# DA_uno_shield_0_9.net
KiCad netlist of a schematic drawn in EAGLE
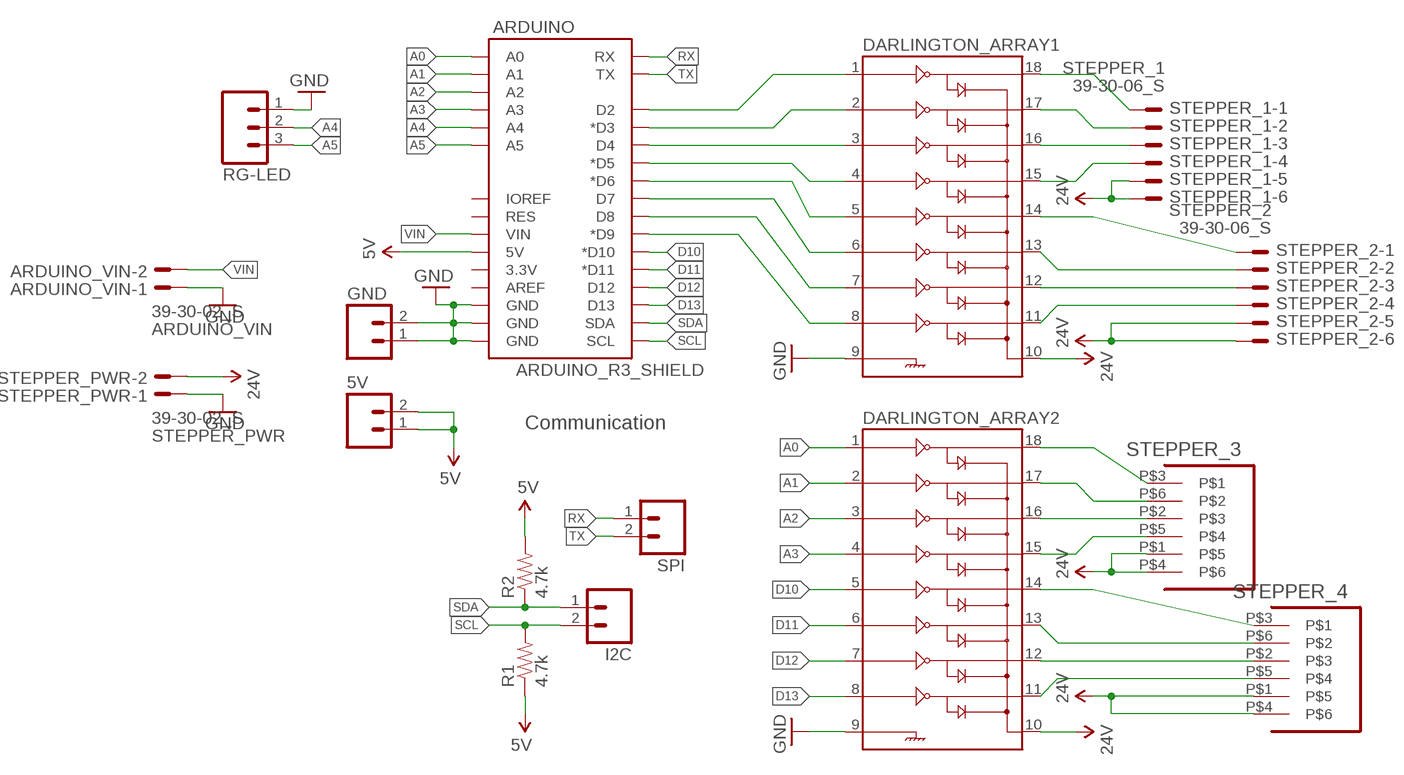
[diagram p0: schematic, sheet 1]

(export (version "E")
  (design (tool "Eeschema 10.0.6"))
  (components
    (comp (ref "5V")
      (value "M021X02_NO_SILK")
      (footprint "eagle-import:1X02_NO_SILK")
      (libsource (lib "eagle-import") (part "M021X02_NO_SILK"))
    )
    (comp (ref "ARDUINO")
      (value "ARDUINO_R3_SHIELD")
      (footprint "eagle-import:UNO_R3_SHIELD")
      (libsource (lib "eagle-import") (part "ARDUINO_R3_SHIELD"))
    )
    (comp (ref "ARDUINO_VIN")
      (value "39-30-02_S")
      (footprint "eagle-import:39-30-_02_")
      (libsource (lib "eagle-import") (part "39-30-?02?_S"))
    )
    (comp (ref "DARLINGTON_ARRAY1")
      (value "ULN2803DIP")
      (footprint "eagle-import:DIL18")
      (libsource (lib "eagle-import") (part "ULN2803DIP"))
    )
    (comp (ref "DARLINGTON_ARRAY2")
      (value "ULN2803DIP")
      (footprint "eagle-import:DIL18")
      (libsource (lib "eagle-import") (part "ULN2803DIP"))
    )
    (comp (ref "GND")
      (value "M021X02_NO_SILK")
      (footprint "eagle-import:1X02_NO_SILK")
      (libsource (lib "eagle-import") (part "M021X02_NO_SILK"))
    )
    (comp (ref "I2C")
      (value "M021X02_NO_SILK")
      (footprint "eagle-import:1X02_NO_SILK")
      (libsource (lib "eagle-import") (part "M021X02_NO_SILK"))
    )
    (comp (ref "R1")
      (value "4.7k")
      (footprint "eagle-import:AXIAL-0.3-KIT")
      (libsource (lib "eagle-import") (part "RESISTORKIT"))
    )
    (comp (ref "R2")
      (value "4.7k")
      (footprint "eagle-import:AXIAL-0.3-KIT")
      (libsource (lib "eagle-import") (part "RESISTORKIT"))
    )
    (comp (ref "RG-LED")
      (value "M03LOCK_NO_SILK")
      (footprint "eagle-import:1X03_LOCK_NO_SILK")
      (libsource (lib "eagle-import") (part "M03LOCK_NO_SILK"))
    )
    (comp (ref "SPI")
      (value "M021X02_NO_SILK")
      (footprint "eagle-import:1X02_NO_SILK")
      (libsource (lib "eagle-import") (part "M021X02_NO_SILK"))
    )
    (comp (ref "STEPPER_1")
      (value "39-30-06_S")
      (footprint "eagle-import:39-30-_06_")
      (libsource (lib "eagle-import") (part "39-30-?06?_S"))
    )
    (comp (ref "STEPPER_2")
      (value "39-30-06_S")
      (footprint "eagle-import:39-30-_06_")
      (libsource (lib "eagle-import") (part "39-30-?06?_S"))
    )
    (comp (ref "STEPPER_3")
      (value "39-29-06")
      (footprint "eagle-import:39-29-_06_")
      (libsource (lib "eagle-import") (part "39-29-?06?"))
    )
    (comp (ref "STEPPER_4")
      (value "39-29-06")
      (footprint "eagle-import:39-29-_06_")
      (libsource (lib "eagle-import") (part "39-29-?06?"))
    )
    (comp (ref "STEPPER_PWR")
      (value "39-30-02_S")
      (footprint "eagle-import:39-30-_02_")
      (libsource (lib "eagle-import") (part "39-30-?02?_S"))
    )
  )
  (nets
    (net (code "1") (name "5V") (class "Default")
      (node (ref "5V") (pin "1") (pinfunction "1_1") (pintype "passive"))
      (node (ref "5V") (pin "2") (pinfunction "2_2") (pintype "passive"))
      (node (ref "ARDUINO") (pin "5V") (pinfunction "5V_5V") (pintype "bidirectional"))
      (node (ref "R1") (pin "P$1") (pinfunction "1_P$1") (pintype "passive"))
      (node (ref "R2") (pin "P$2") (pinfunction "2_P$2") (pintype "passive"))
    )
    (net (code "2") (name "24V") (class "Default")
      (node (ref "DARLINGTON_ARRAY1") (pin "10") (pinfunction "10_10") (pintype "bidirectional"))
      (node (ref "DARLINGTON_ARRAY2") (pin "10") (pinfunction "10_10") (pintype "bidirectional"))
      (node (ref "STEPPER_1") (pin "5") (pinfunction "P_5") (pintype "passive"))
      (node (ref "STEPPER_1") (pin "6") (pinfunction "P_6") (pintype "passive"))
      (node (ref "STEPPER_2") (pin "5") (pinfunction "P_5") (pintype "passive"))
      (node (ref "STEPPER_2") (pin "6") (pinfunction "P_6") (pintype "passive"))
      (node (ref "STEPPER_3") (pin "P$1") (pinfunction "P$5_P$1") (pintype "bidirectional"))
      (node (ref "STEPPER_3") (pin "P$4") (pinfunction "P$6_P$4") (pintype "bidirectional"))
      (node (ref "STEPPER_4") (pin "P$1") (pinfunction "P$5_P$1") (pintype "bidirectional"))
      (node (ref "STEPPER_4") (pin "P$4") (pinfunction "P$6_P$4") (pintype "bidirectional"))
      (node (ref "STEPPER_PWR") (pin "2") (pinfunction "P_2") (pintype "passive"))
    )
    (net (code "3") (name "A0") (class "Default")
      (node (ref "ARDUINO") (pin "A0") (pinfunction "A0_A0") (pintype "bidirectional"))
      (node (ref "DARLINGTON_ARRAY2") (pin "1") (pinfunction "1_1") (pintype "bidirectional"))
    )
    (net (code "4") (name "A1") (class "Default")
      (node (ref "ARDUINO") (pin "A1") (pinfunction "A1_A1") (pintype "bidirectional"))
      (node (ref "DARLINGTON_ARRAY2") (pin "2") (pinfunction "2_2") (pintype "bidirectional"))
    )
    (net (code "5") (name "A2") (class "Default")
      (node (ref "ARDUINO") (pin "A2") (pinfunction "A2_A2") (pintype "bidirectional"))
      (node (ref "DARLINGTON_ARRAY2") (pin "3") (pinfunction "3_3") (pintype "bidirectional"))
    )
    (net (code "6") (name "A3") (class "Default")
      (node (ref "ARDUINO") (pin "A3") (pinfunction "A3_A3") (pintype "bidirectional"))
      (node (ref "DARLINGTON_ARRAY2") (pin "4") (pinfunction "4_4") (pintype "bidirectional"))
    )
    (net (code "7") (name "A4") (class "Default")
      (node (ref "ARDUINO") (pin "A4") (pinfunction "A4_A4") (pintype "bidirectional"))
      (node (ref "RG-LED") (pin "2") (pinfunction "2_2") (pintype "passive"))
    )
    (net (code "8") (name "A5") (class "Default")
      (node (ref "ARDUINO") (pin "A5") (pinfunction "A5_A5") (pintype "bidirectional"))
      (node (ref "RG-LED") (pin "3") (pinfunction "3_3") (pintype "passive"))
    )
    (net (code "9") (name "D10") (class "Default")
      (node (ref "ARDUINO") (pin "D10") (pinfunction "*D10_D10") (pintype "bidirectional"))
      (node (ref "DARLINGTON_ARRAY2") (pin "5") (pinfunction "5_5") (pintype "bidirectional"))
    )
    (net (code "10") (name "D11") (class "Default")
      (node (ref "ARDUINO") (pin "D11") (pinfunction "*D11_D11") (pintype "bidirectional"))
      (node (ref "DARLINGTON_ARRAY2") (pin "6") (pinfunction "6_6") (pintype "bidirectional"))
    )
    (net (code "11") (name "D12") (class "Default")
      (node (ref "ARDUINO") (pin "D12") (pinfunction "D12_D12") (pintype "bidirectional"))
      (node (ref "DARLINGTON_ARRAY2") (pin "7") (pinfunction "7_7") (pintype "bidirectional"))
    )
    (net (code "12") (name "D13") (class "Default")
      (node (ref "ARDUINO") (pin "D13") (pinfunction "D13_D13") (pintype "bidirectional"))
      (node (ref "DARLINGTON_ARRAY2") (pin "8") (pinfunction "8_8") (pintype "bidirectional"))
    )
    (net (code "13") (name "GND") (class "Default")
      (node (ref "ARDUINO") (pin "GND@0") (pinfunction "GND_GND@0") (pintype "bidirectional"))
      (node (ref "ARDUINO") (pin "GND@1") (pinfunction "GND_GND@1") (pintype "bidirectional"))
      (node (ref "ARDUINO") (pin "GND@2") (pinfunction "GND_GND@2") (pintype "bidirectional"))
      (node (ref "ARDUINO_VIN") (pin "1") (pinfunction "P_1") (pintype "passive"))
      (node (ref "DARLINGTON_ARRAY1") (pin "9") (pinfunction "9_9") (pintype "bidirectional"))
      (node (ref "DARLINGTON_ARRAY2") (pin "9") (pinfunction "9_9") (pintype "bidirectional"))
      (node (ref "GND") (pin "1") (pinfunction "1_1") (pintype "passive"))
      (node (ref "GND") (pin "2") (pinfunction "2_2") (pintype "passive"))
      (node (ref "RG-LED") (pin "1") (pinfunction "1_1") (pintype "passive"))
      (node (ref "STEPPER_PWR") (pin "1") (pinfunction "P_1") (pintype "passive"))
    )
    (net (code "14") (name "Net-(ARDUINO-*D3)") (class "Default")
      (node (ref "ARDUINO") (pin "D3") (pinfunction "*D3_D3") (pintype "bidirectional"))
      (node (ref "DARLINGTON_ARRAY1") (pin "2") (pinfunction "2_2") (pintype "bidirectional"))
    )
    (net (code "15") (name "Net-(ARDUINO-*D5)") (class "Default")
      (node (ref "ARDUINO") (pin "D5") (pinfunction "*D5_D5") (pintype "bidirectional"))
      (node (ref "DARLINGTON_ARRAY1") (pin "4") (pinfunction "4_4") (pintype "bidirectional"))
    )
    (net (code "16") (name "Net-(ARDUINO-*D6)") (class "Default")
      (node (ref "ARDUINO") (pin "D6") (pinfunction "*D6_D6") (pintype "bidirectional"))
      (node (ref "DARLINGTON_ARRAY1") (pin "5") (pinfunction "5_5") (pintype "bidirectional"))
    )
    (net (code "17") (name "Net-(ARDUINO-*D9)") (class "Default")
      (node (ref "ARDUINO") (pin "D9") (pinfunction "*D9_D9") (pintype "bidirectional"))
      (node (ref "DARLINGTON_ARRAY1") (pin "8") (pinfunction "8_8") (pintype "bidirectional"))
    )
    (net (code "18") (name "Net-(ARDUINO-PadD2)") (class "Default")
      (node (ref "ARDUINO") (pin "D2") (pinfunction "D2_D2") (pintype "bidirectional"))
      (node (ref "DARLINGTON_ARRAY1") (pin "1") (pinfunction "1_1") (pintype "bidirectional"))
    )
    (net (code "19") (name "Net-(ARDUINO-PadD4)") (class "Default")
      (node (ref "ARDUINO") (pin "D4") (pinfunction "D4_D4") (pintype "bidirectional"))
      (node (ref "DARLINGTON_ARRAY1") (pin "3") (pinfunction "3_3") (pintype "bidirectional"))
    )
    (net (code "20") (name "Net-(ARDUINO-PadD7)") (class "Default")
      (node (ref "ARDUINO") (pin "D7") (pinfunction "D7_D7") (pintype "bidirectional"))
      (node (ref "DARLINGTON_ARRAY1") (pin "6") (pinfunction "6_6") (pintype "bidirectional"))
    )
    (net (code "21") (name "Net-(ARDUINO-PadD8)") (class "Default")
      (node (ref "ARDUINO") (pin "D8") (pinfunction "D8_D8") (pintype "bidirectional"))
      (node (ref "DARLINGTON_ARRAY1") (pin "7") (pinfunction "7_7") (pintype "bidirectional"))
    )
    (net (code "22") (name "Net-(STEPPER_1A-P)") (class "Default")
      (node (ref "DARLINGTON_ARRAY1") (pin "18") (pinfunction "18_18") (pintype "bidirectional"))
      (node (ref "STEPPER_1") (pin "1") (pinfunction "P_1") (pintype "passive"))
    )
    (net (code "23") (name "Net-(STEPPER_1B-P)") (class "Default")
      (node (ref "DARLINGTON_ARRAY1") (pin "17") (pinfunction "17_17") (pintype "bidirectional"))
      (node (ref "STEPPER_1") (pin "2") (pinfunction "P_2") (pintype "passive"))
    )
    (net (code "24") (name "Net-(STEPPER_1C-P)") (class "Default")
      (node (ref "DARLINGTON_ARRAY1") (pin "16") (pinfunction "16_16") (pintype "bidirectional"))
      (node (ref "STEPPER_1") (pin "3") (pinfunction "P_3") (pintype "passive"))
    )
    (net (code "25") (name "Net-(STEPPER_1D-P)") (class "Default")
      (node (ref "DARLINGTON_ARRAY1") (pin "15") (pinfunction "15_15") (pintype "bidirectional"))
      (node (ref "STEPPER_1") (pin "4") (pinfunction "P_4") (pintype "passive"))
    )
    (net (code "26") (name "Net-(STEPPER_2A-P)") (class "Default")
      (node (ref "DARLINGTON_ARRAY1") (pin "14") (pinfunction "14_14") (pintype "bidirectional"))
      (node (ref "STEPPER_2") (pin "1") (pinfunction "P_1") (pintype "passive"))
    )
    (net (code "27") (name "Net-(STEPPER_2B-P)") (class "Default")
      (node (ref "DARLINGTON_ARRAY1") (pin "13") (pinfunction "13_13") (pintype "bidirectional"))
      (node (ref "STEPPER_2") (pin "2") (pinfunction "P_2") (pintype "passive"))
    )
    (net (code "28") (name "Net-(STEPPER_2C-P)") (class "Default")
      (node (ref "DARLINGTON_ARRAY1") (pin "12") (pinfunction "12_12") (pintype "bidirectional"))
      (node (ref "STEPPER_2") (pin "3") (pinfunction "P_3") (pintype "passive"))
    )
    (net (code "29") (name "Net-(STEPPER_2D-P)") (class "Default")
      (node (ref "DARLINGTON_ARRAY1") (pin "11") (pinfunction "11_11") (pintype "bidirectional"))
      (node (ref "STEPPER_2") (pin "4") (pinfunction "P_4") (pintype "passive"))
    )
    (net (code "30") (name "Net-(STEPPER_3-P$1)") (class "Default")
      (node (ref "DARLINGTON_ARRAY2") (pin "18") (pinfunction "18_18") (pintype "bidirectional"))
      (node (ref "STEPPER_3") (pin "P$3") (pinfunction "P$1_P$3") (pintype "bidirectional"))
    )
    (net (code "31") (name "Net-(STEPPER_3-P$2)") (class "Default")
      (node (ref "DARLINGTON_ARRAY2") (pin "17") (pinfunction "17_17") (pintype "bidirectional"))
      (node (ref "STEPPER_3") (pin "P$6") (pinfunction "P$2_P$6") (pintype "bidirectional"))
    )
    (net (code "32") (name "Net-(STEPPER_3-P$3)") (class "Default")
      (node (ref "DARLINGTON_ARRAY2") (pin "16") (pinfunction "16_16") (pintype "bidirectional"))
      (node (ref "STEPPER_3") (pin "P$2") (pinfunction "P$3_P$2") (pintype "bidirectional"))
    )
    (net (code "33") (name "Net-(STEPPER_3-P$4)") (class "Default")
      (node (ref "DARLINGTON_ARRAY2") (pin "15") (pinfunction "15_15") (pintype "bidirectional"))
      (node (ref "STEPPER_3") (pin "P$5") (pinfunction "P$4_P$5") (pintype "bidirectional"))
    )
    (net (code "34") (name "Net-(STEPPER_4-P$1)") (class "Default")
      (node (ref "DARLINGTON_ARRAY2") (pin "14") (pinfunction "14_14") (pintype "bidirectional"))
      (node (ref "STEPPER_4") (pin "P$3") (pinfunction "P$1_P$3") (pintype "bidirectional"))
    )
    (net (code "35") (name "Net-(STEPPER_4-P$2)") (class "Default")
      (node (ref "DARLINGTON_ARRAY2") (pin "13") (pinfunction "13_13") (pintype "bidirectional"))
      (node (ref "STEPPER_4") (pin "P$6") (pinfunction "P$2_P$6") (pintype "bidirectional"))
    )
    (net (code "36") (name "Net-(STEPPER_4-P$3)") (class "Default")
      (node (ref "DARLINGTON_ARRAY2") (pin "12") (pinfunction "12_12") (pintype "bidirectional"))
      (node (ref "STEPPER_4") (pin "P$2") (pinfunction "P$3_P$2") (pintype "bidirectional"))
    )
    (net (code "37") (name "Net-(STEPPER_4-P$4)") (class "Default")
      (node (ref "DARLINGTON_ARRAY2") (pin "11") (pinfunction "11_11") (pintype "bidirectional"))
      (node (ref "STEPPER_4") (pin "P$5") (pinfunction "P$4_P$5") (pintype "bidirectional"))
    )
    (net (code "38") (name "RX") (class "Default")
      (node (ref "ARDUINO") (pin "RX") (pinfunction "RX_RX") (pintype "bidirectional"))
      (node (ref "SPI") (pin "1") (pinfunction "1_1") (pintype "passive"))
    )
    (net (code "39") (name "SCL") (class "Default")
      (node (ref "ARDUINO") (pin "SCL") (pinfunction "SCL_SCL") (pintype "bidirectional"))
      (node (ref "I2C") (pin "2") (pinfunction "2_2") (pintype "passive"))
      (node (ref "R1") (pin "P$2") (pinfunction "2_P$2") (pintype "passive"))
    )
    (net (code "40") (name "SDA") (class "Default")
      (node (ref "ARDUINO") (pin "SDA") (pinfunction "SDA_SDA") (pintype "bidirectional"))
      (node (ref "I2C") (pin "1") (pinfunction "1_1") (pintype "passive"))
      (node (ref "R2") (pin "P$1") (pinfunction "1_P$1") (pintype "passive"))
    )
    (net (code "41") (name "TX") (class "Default")
      (node (ref "ARDUINO") (pin "TX") (pinfunction "TX_TX") (pintype "bidirectional"))
      (node (ref "SPI") (pin "2") (pinfunction "2_2") (pintype "passive"))
    )
    (net (code "42") (name "VIN") (class "Default")
      (node (ref "ARDUINO") (pin "VIN") (pinfunction "VIN_VIN") (pintype "bidirectional"))
      (node (ref "ARDUINO_VIN") (pin "2") (pinfunction "P_2") (pintype "passive"))
    )
    (net (code "43") (name "unconnected-(ARDUINO-Pad3.3V)") (class "Default")
      (node (ref "ARDUINO") (pin "3.3V") (pinfunction "3.3V_3.3V") (pintype "bidirectional"))
    )
    (net (code "44") (name "unconnected-(ARDUINO-PadAREF)") (class "Default")
      (node (ref "ARDUINO") (pin "AREF") (pinfunction "AREF_AREF") (pintype "bidirectional"))
    )
    (net (code "45") (name "unconnected-(ARDUINO-PadIOREF)") (class "Default")
      (node (ref "ARDUINO") (pin "IOREF") (pinfunction "IOREF_IOREF") (pintype "bidirectional"))
    )
    (net (code "46") (name "unconnected-(ARDUINO-PadRES)") (class "Default")
      (node (ref "ARDUINO") (pin "RES") (pinfunction "RES_RES") (pintype "bidirectional"))
    )
  )
)
